# USB.net
KiCad netlist of a schematic drawn in Altium Designer
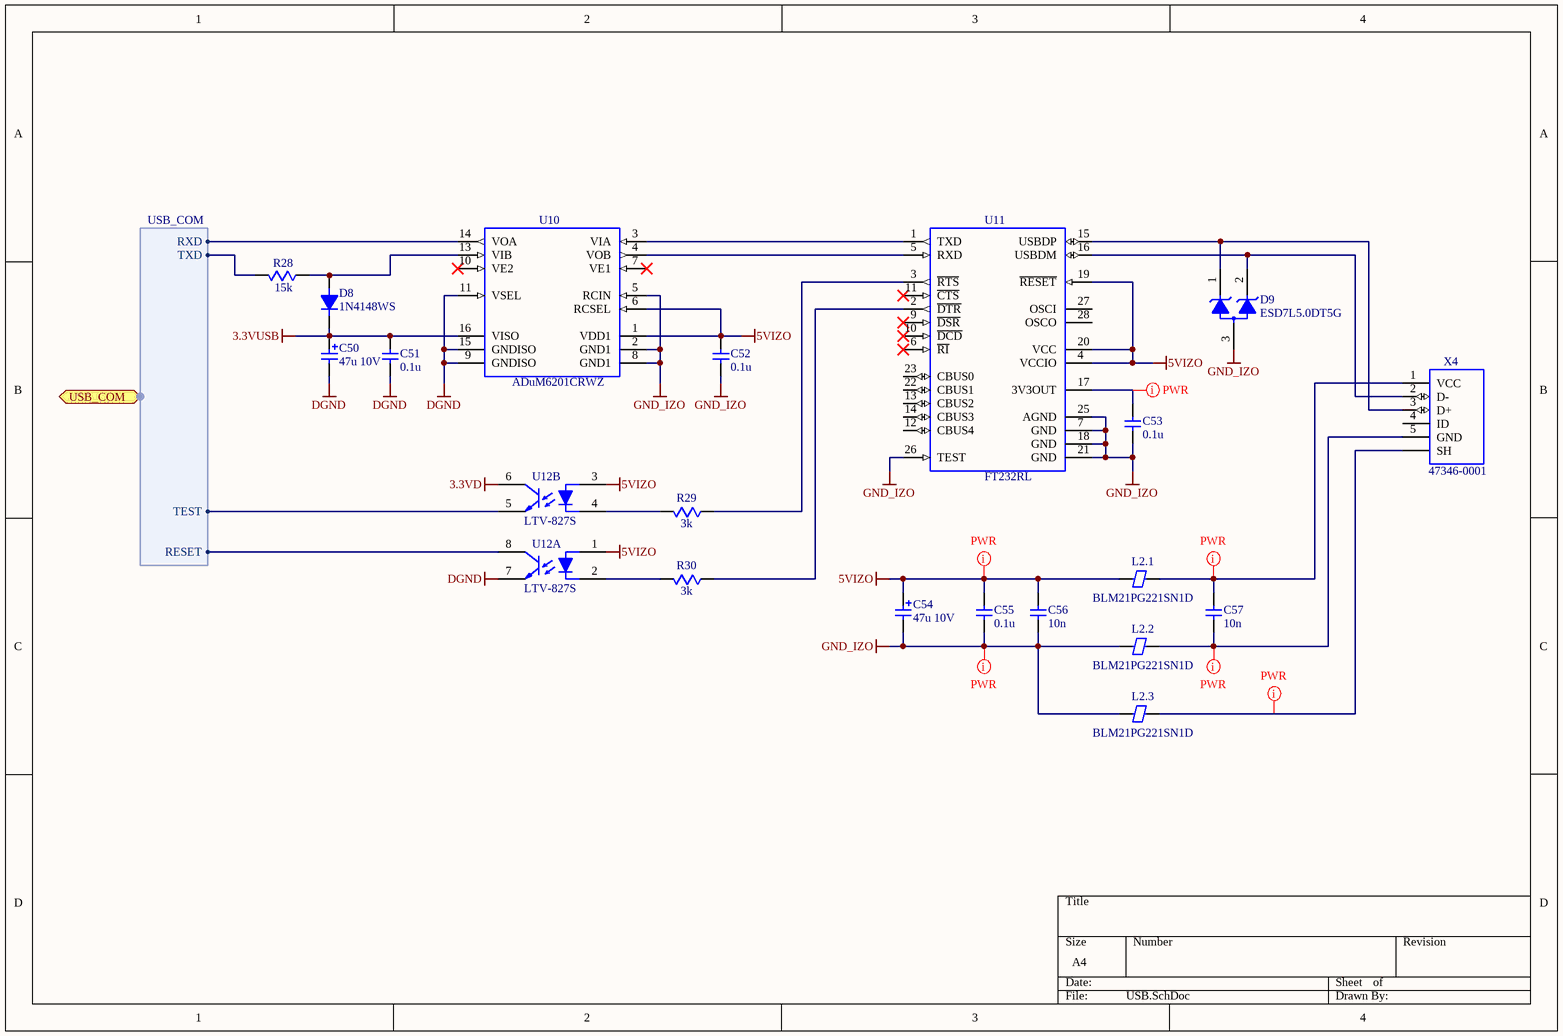
[diagram p0: USB.SchDoc]

(export (version "E")
  (design (tool "Eeschema 10.0.6"))
  (components
    (comp (ref "C50")
      (value "47u 10V")
      (footprint "SMD/C/TAJ-B")
      (libsource (lib "My_lib") (part "Capacitor Pol"))
    )
    (comp (ref "C51") (value "0.1u") (footprint "SMD/C/0603") (libsource (lib "My_lib") (part "Capacitor")))
    (comp (ref "C52") (value "0.1u") (footprint "SMD/C/0603") (libsource (lib "My_lib") (part "Capacitor")))
    (comp (ref "C53") (value "0.1u") (footprint "SMD/C/0603") (libsource (lib "My_lib") (part "Capacitor")))
    (comp (ref "C54")
      (value "47u 10V")
      (footprint "SMD/C/TAJ-B")
      (libsource (lib "My_lib") (part "Capacitor Pol"))
    )
    (comp (ref "C55") (value "0.1u") (footprint "SMD/C/0603") (libsource (lib "My_lib") (part "Capacitor")))
    (comp (ref "C56") (value "10n") (footprint "SMD/C/0603") (libsource (lib "My_lib") (part "Capacitor")))
    (comp (ref "C57") (value "10n") (footprint "SMD/C/0603") (libsource (lib "My_lib") (part "Capacitor")))
    (comp (ref "D8") (value "1N4148WS") (footprint "SMD/SOD-323") (libsource (lib "My_lib") (part "Diode")))
    (comp (ref "D9")
      (value "ESD7L5.0DT5G")
      (footprint "SMD/SOT723")
      (description "ESD Protection Diodes with Ultra?Low Capacitance")
      (libsource (lib "My_lib") (part "ESD7L5.0DT5G"))
    )
    (comp (ref "L2.1")
      (value "BLM21PG221SN1D")
      (footprint "SMD/C/0805")
      (libsource (lib "My_lib") (part "BLM21PG221SN1D"))
    )
    (comp (ref "L2.2")
      (value "BLM21PG221SN1D")
      (footprint "SMD/C/0805")
      (libsource (lib "My_lib") (part "BLM21PG221SN1D"))
    )
    (comp (ref "L2.3")
      (value "BLM21PG221SN1D")
      (footprint "SMD/C/0805")
      (libsource (lib "My_lib") (part "BLM21PG221SN1D"))
    )
    (comp (ref "R28") (value "15k") (footprint "SMD/R/0603") (libsource (lib "My_lib") (part "Resistor")))
    (comp (ref "R29") (value "3k") (footprint "SMD/R/0603") (libsource (lib "My_lib") (part "Resistor")))
    (comp (ref "R30") (value "3k") (footprint "SMD/R/0603") (libsource (lib "My_lib") (part "Resistor")))
    (comp (ref "U10")
      (value "ADuM6201CRWZ")
      (footprint "SMD/SOIC16/1.27MMP/7.5x10.3mm/10.6MMWP")
      (description "Dual-Channel, 5 kV Isolators with Integrated DC-to-DC Converter")
      (libsource (lib "My_lib") (part "ADuM6201"))
    )
    (comp (ref "U11")
      (value "FT232RL")
      (footprint "SMD/SOP28/0.65MMP/5.3x10.2mm/7.9MMWP")
      (description "USB to RS232 / RS422 / RS485 Converters")
      (libsource (lib "My_lib") (part "FT232RL"))
    )
    (comp (ref "U12")
      (value "LTV-827S")
      (footprint "SMD/DIP8/2.54MMP/9.68x6.5MM/10.16MMWP")
      (libsource (lib "My_lib") (part "LTV-827S"))
    )
    (comp (ref "X4")
      (value "47346-0001")
      (footprint "47346-0001")
      (description "USB Connector")
      (libsource (lib "My_lib") (part "MicroUSB Connector"))
    )
  )
  (nets
    (net (code "2") (name "/RESET") (class "Default")
      (node (ref "U12") (pin "8") (pinfunction "C_8") (pintype "passive"))
    )
    (net (code "3") (name "/RXD") (class "Default")
      (node (ref "U10") (pin "14") (pinfunction "VOA_14") (pintype "output"))
    )
    (net (code "4") (name "/TEST") (class "Default")
      (node (ref "U12") (pin "5") (pinfunction "E_5") (pintype "passive"))
    )
    (net (code "5") (name "/TXD") (class "Default")
      (node (ref "R28") (pin "2") (pinfunction "2_2") (pintype "passive"))
    )
    (net (code "7") (name "3.3VD") (class "Default")
      (node (ref "U12") (pin "6") (pinfunction "C_6") (pintype "passive"))
    )
    (net (code "8") (name "3.3VUSB") (class "Default")
      (node (ref "C50") (pin "P") (pinfunction "P_P") (pintype "passive"))
      (node (ref "C51") (pin "2") (pinfunction "2_2") (pintype "passive"))
      (node (ref "D8") (pin "C") (pinfunction "C_C") (pintype "passive"))
      (node (ref "U10") (pin "16") (pinfunction "VISO_16") (pintype "power_in"))
    )
    (net (code "9") (name "5VIZO") (class "Default")
      (node (ref "C52") (pin "2") (pinfunction "2_2") (pintype "passive"))
      (node (ref "C54") (pin "P") (pinfunction "P_P") (pintype "passive"))
      (node (ref "C55") (pin "2") (pinfunction "2_2") (pintype "passive"))
      (node (ref "C56") (pin "2") (pinfunction "2_2") (pintype "passive"))
      (node (ref "L2.1") (pin "1") (pinfunction "1_1") (pintype "passive"))
      (node (ref "U10") (pin "1") (pinfunction "VDD1_1") (pintype "power_in"))
      (node (ref "U10") (pin "6") (pinfunction "RCSEL_6") (pintype "input"))
      (node (ref "U11") (pin "19") (pinfunction "~{RESET}_19") (pintype "input"))
      (node (ref "U11") (pin "20") (pinfunction "VCC_20") (pintype "power_in"))
      (node (ref "U11") (pin "4") (pinfunction "VCCIO_4") (pintype "power_in"))
      (node (ref "U12") (pin "1") (pinfunction "A_1") (pintype "passive"))
      (node (ref "U12") (pin "3") (pinfunction "A_3") (pintype "passive"))
    )
    (net (code "10") (name "DGND") (class "Default")
      (node (ref "C50") (pin "M") (pinfunction "M_M") (pintype "passive"))
      (node (ref "C51") (pin "1") (pinfunction "1_1") (pintype "passive"))
      (node (ref "U10") (pin "11") (pinfunction "VSEL_11") (pintype "input"))
      (node (ref "U10") (pin "15") (pinfunction "GNDISO_15") (pintype "power_in"))
      (node (ref "U10") (pin "9") (pinfunction "GNDISO_9") (pintype "power_in"))
      (node (ref "U12") (pin "7") (pinfunction "E_7") (pintype "passive"))
    )
    (net (code "11") (name "GND_IZO") (class "Default")
      (node (ref "C52") (pin "1") (pinfunction "1_1") (pintype "passive"))
      (node (ref "C53") (pin "1") (pinfunction "1_1") (pintype "passive"))
      (node (ref "C54") (pin "M") (pinfunction "M_M") (pintype "passive"))
      (node (ref "C55") (pin "1") (pinfunction "1_1") (pintype "passive"))
      (node (ref "C56") (pin "1") (pinfunction "1_1") (pintype "passive"))
      (node (ref "D9") (pin "3") (pinfunction "3_3") (pintype "passive"))
      (node (ref "L2.2") (pin "1") (pinfunction "1_1") (pintype "passive"))
      (node (ref "L2.3") (pin "1") (pinfunction "1_1") (pintype "passive"))
      (node (ref "U10") (pin "2") (pinfunction "GND1_2") (pintype "power_in"))
      (node (ref "U10") (pin "5") (pinfunction "RCIN_5") (pintype "input"))
      (node (ref "U10") (pin "8") (pinfunction "GND1_8") (pintype "power_in"))
      (node (ref "U11") (pin "18") (pinfunction "GND_18") (pintype "power_in"))
      (node (ref "U11") (pin "21") (pinfunction "GND_21") (pintype "power_in"))
      (node (ref "U11") (pin "25") (pinfunction "AGND_25") (pintype "power_in"))
      (node (ref "U11") (pin "26") (pinfunction "TEST_26") (pintype "input"))
      (node (ref "U11") (pin "7") (pinfunction "GND_7") (pintype "power_in"))
    )
    (net (code "12") (name "Net-(R29-Pad2)") (class "Default")
      (node (ref "R29") (pin "2") (pinfunction "2_2") (pintype "passive"))
      (node (ref "U12") (pin "4") (pinfunction "C_4") (pintype "passive"))
    )
    (net (code "13") (name "Net-(R30-Pad2)") (class "Default")
      (node (ref "R30") (pin "2") (pinfunction "2_2") (pintype "passive"))
      (node (ref "U12") (pin "2") (pinfunction "C_2") (pintype "passive"))
    )
    (net (code "14") (name "Net-(U10-VIA)") (class "Default")
      (node (ref "U10") (pin "3") (pinfunction "VIA_3") (pintype "input"))
      (node (ref "U11") (pin "1") (pinfunction "TXD_1") (pintype "output"))
    )
    (net (code "15") (name "Net-(U10-VIB)") (class "Default")
      (node (ref "D8") (pin "A") (pinfunction "A_A") (pintype "passive"))
      (node (ref "R28") (pin "1") (pinfunction "1_1") (pintype "passive"))
      (node (ref "U10") (pin "13") (pinfunction "VIB_13") (pintype "input"))
    )
    (net (code "16") (name "Net-(U10-VOB)") (class "Default")
      (node (ref "U10") (pin "4") (pinfunction "VOB_4") (pintype "output"))
      (node (ref "U11") (pin "5") (pinfunction "RXD_5") (pintype "input"))
    )
    (net (code "17") (name "Net-(U11-3V3OUT)") (class "Default")
      (node (ref "C53") (pin "2") (pinfunction "2_2") (pintype "passive"))
      (node (ref "U11") (pin "17") (pinfunction "3V3OUT_17") (pintype "power_in"))
    )
    (net (code "18") (name "Net-(U11-USBDM)") (class "Default")
      (node (ref "D9") (pin "2") (pinfunction "2_2") (pintype "passive"))
      (node (ref "U11") (pin "16") (pinfunction "USBDM_16") (pintype "bidirectional"))
      (node (ref "X4") (pin "2") (pinfunction "D-_2") (pintype "bidirectional"))
    )
    (net (code "19") (name "Net-(U11-USBDP)") (class "Default")
      (node (ref "D9") (pin "1") (pinfunction "1_1") (pintype "passive"))
      (node (ref "U11") (pin "15") (pinfunction "USBDP_15") (pintype "bidirectional"))
      (node (ref "X4") (pin "3") (pinfunction "D+_3") (pintype "bidirectional"))
    )
    (net (code "20") (name "Net-(U11-~{DTR})") (class "Default")
      (node (ref "R30") (pin "1") (pinfunction "1_1") (pintype "passive"))
      (node (ref "U11") (pin "2") (pinfunction "~{DTR}_2") (pintype "output"))
    )
    (net (code "21") (name "Net-(U11-~{RTS})") (class "Default")
      (node (ref "R29") (pin "1") (pinfunction "1_1") (pintype "passive"))
      (node (ref "U11") (pin "3") (pinfunction "~{RTS}_3") (pintype "output"))
    )
    (net (code "22") (name "Net-(X4-GND)") (class "Default")
      (node (ref "C57") (pin "1") (pinfunction "1_1") (pintype "passive"))
      (node (ref "L2.2") (pin "2") (pinfunction "2_2") (pintype "passive"))
      (node (ref "X4") (pin "5") (pinfunction "GND_5") (pintype "power_in"))
    )
    (net (code "23") (name "Net-(X4-SH)") (class "Default")
      (node (ref "L2.3") (pin "2") (pinfunction "2_2") (pintype "passive"))
      (node (ref "X4") (pin "CASE") (pinfunction "SH_CASE") (pintype "power_in"))
    )
    (net (code "24") (name "Net-(X4-VCC)") (class "Default")
      (node (ref "C57") (pin "2") (pinfunction "2_2") (pintype "passive"))
      (node (ref "L2.1") (pin "2") (pinfunction "2_2") (pintype "passive"))
      (node (ref "X4") (pin "1") (pinfunction "VCC_1") (pintype "power_in"))
    )
    (net (code "25") (name "unconnected-(U10-VE1-Pad7)") (class "Default")
      (node (ref "U10") (pin "7") (pinfunction "VE1_7") (pintype "input+no_connect"))
    )
    (net (code "26") (name "unconnected-(U10-VE2-Pad10)") (class "Default")
      (node (ref "U10") (pin "10") (pinfunction "VE2_10") (pintype "input+no_connect"))
    )
    (net (code "27") (name "unconnected-(U11-CBUS0-Pad23)") (class "Default")
      (node (ref "U11") (pin "23") (pinfunction "CBUS0_23") (pintype "bidirectional"))
    )
    (net (code "28") (name "unconnected-(U11-CBUS1-Pad22)") (class "Default")
      (node (ref "U11") (pin "22") (pinfunction "CBUS1_22") (pintype "bidirectional"))
    )
    (net (code "29") (name "unconnected-(U11-CBUS2-Pad13)") (class "Default")
      (node (ref "U11") (pin "13") (pinfunction "CBUS2_13") (pintype "bidirectional"))
    )
    (net (code "30") (name "unconnected-(U11-CBUS3-Pad14)") (class "Default")
      (node (ref "U11") (pin "14") (pinfunction "CBUS3_14") (pintype "bidirectional"))
    )
    (net (code "31") (name "unconnected-(U11-CBUS4-Pad12)") (class "Default")
      (node (ref "U11") (pin "12") (pinfunction "CBUS4_12") (pintype "bidirectional"))
    )
    (net (code "32") (name "unconnected-(U11-OSCI-Pad27)") (class "Default")
      (node (ref "U11") (pin "27") (pinfunction "OSCI_27") (pintype "passive"))
    )
    (net (code "33") (name "unconnected-(U11-OSCO-Pad28)") (class "Default")
      (node (ref "U11") (pin "28") (pinfunction "OSCO_28") (pintype "passive"))
    )
    (net (code "34") (name "unconnected-(U11-~{CTS}-Pad11)") (class "Default")
      (node (ref "U11") (pin "11") (pinfunction "~{CTS}_11") (pintype "input+no_connect"))
    )
    (net (code "35") (name "unconnected-(U11-~{DCD}-Pad10)") (class "Default")
      (node (ref "U11") (pin "10") (pinfunction "~{DCD}_10") (pintype "input+no_connect"))
    )
    (net (code "36") (name "unconnected-(U11-~{DSR}-Pad9)") (class "Default")
      (node (ref "U11") (pin "9") (pinfunction "~{DSR}_9") (pintype "input+no_connect"))
    )
    (net (code "37") (name "unconnected-(U11-~{RI}-Pad6)") (class "Default")
      (node (ref "U11") (pin "6") (pinfunction "~{RI}_6") (pintype "input+no_connect"))
    )
    (net (code "38") (name "unconnected-(X4-ID-Pad4)") (class "Default")
      (node (ref "X4") (pin "4") (pinfunction "ID_4") (pintype "passive"))
    )
  )
)
